# main.net
KiCad netlist of a schematic drawn in Altium Designer
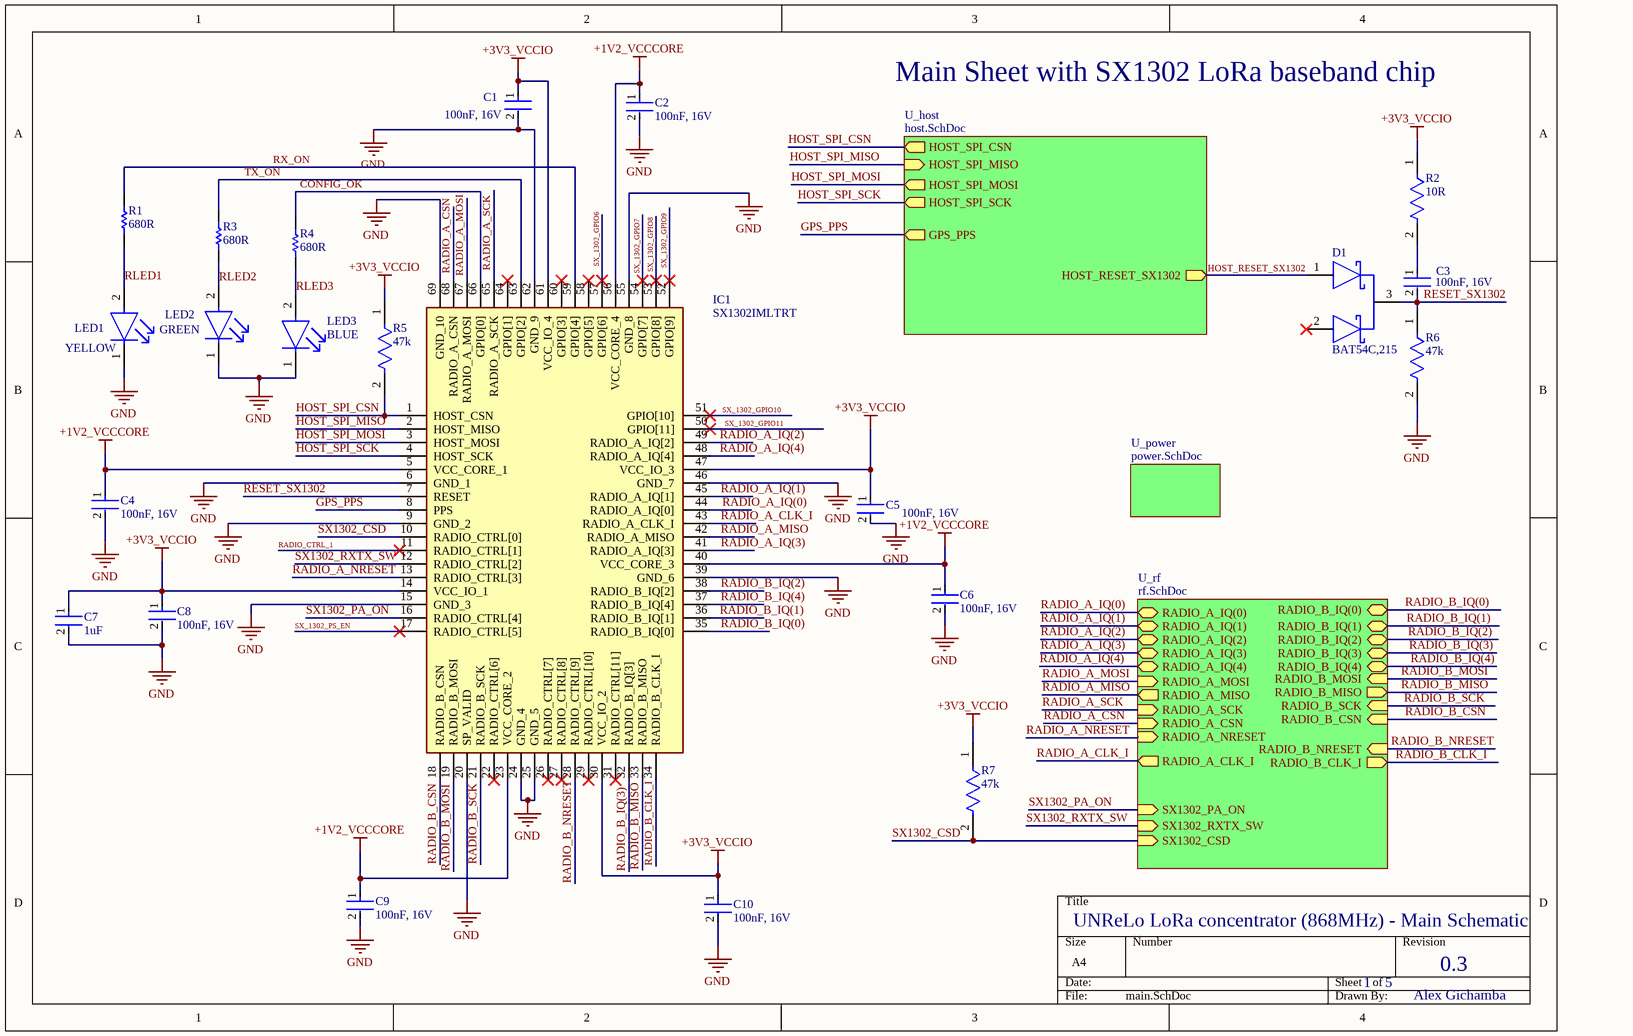
[diagram p0: main.SchDoc]

(export (version "E")
  (design (tool "Eeschema 10.0.6"))
  (components
    (comp (ref "C1")
      (value "100nF, 16V")
      (footprint "FP-CC0603-DA-MFG")
      (description "CAP CER 0.1UF 50V X7R 0603")
      (fields (field (name "MANUFACTURER") "YAGEO") (field (name "VOLTAGE") "50 V"))
      (libsource (lib "Altium Content Vault") (part "11868f565c42a9108669ba33697ecf6"))
    )
    (comp (ref "C2")
      (value "100nF, 16V")
      (footprint "FP-CC0603-DA-MFG")
      (description "CAP CER 0.1UF 50V X7R 0603")
      (fields (field (name "MANUFACTURER") "YAGEO") (field (name "VOLTAGE") "50 V"))
      (libsource (lib "Altium Content Vault") (part "11868f565c42a9108669ba33697ecf6"))
    )
    (comp (ref "C3")
      (value "100nF, 16V")
      (footprint "FP-CC0603-DA-MFG")
      (description "CAP CER 0.1UF 50V X7R 0603")
      (fields (field (name "MANUFACTURER") "YAGEO") (field (name "VOLTAGE") "50 V"))
      (libsource (lib "Altium Content Vault") (part "11868f565c42a9108669ba33697ecf6"))
    )
    (comp (ref "C4")
      (value "100nF, 16V")
      (footprint "FP-CC0603-DA-MFG")
      (description "CAP CER 0.1UF 50V X7R 0603")
      (fields (field (name "MANUFACTURER") "YAGEO") (field (name "VOLTAGE") "50 V"))
      (libsource (lib "Altium Content Vault") (part "11868f565c42a9108669ba33697ecf6"))
    )
    (comp (ref "C5")
      (value "100nF, 16V")
      (footprint "FP-CC0603-DA-MFG")
      (description "CAP CER 0.1UF 50V X7R 0603")
      (fields (field (name "MANUFACTURER") "YAGEO") (field (name "VOLTAGE") "50 V"))
      (libsource (lib "Altium Content Vault") (part "11868f565c42a9108669ba33697ecf6"))
    )
    (comp (ref "C6")
      (value "100nF, 16V")
      (footprint "FP-CC0603-DA-MFG")
      (description "CAP CER 0.1UF 50V X7R 0603")
      (fields (field (name "MANUFACTURER") "YAGEO") (field (name "VOLTAGE") "50 V"))
      (libsource (lib "Altium Content Vault") (part "11868f565c42a9108669ba33697ecf6"))
    )
    (comp (ref "C7")
      (value "1uF")
      (footprint "FP-CL21-IPC_A")
      (description "CL21 Series 0805 1uF 16V ±10% Tolerance X7R Multilayer Ceramic Chip Capacitor")
      (fields (field (name "TOLERANCE") "10%") (field (name "VOLTAGE") "16V"))
      (libsource (lib "Altium Content Vault") (part "b4654b650e69147ec39a6b967a45e02"))
    )
    (comp (ref "C8")
      (value "100nF, 16V")
      (footprint "FP-CC0603-DA-MFG")
      (description "CAP CER 0.1UF 50V X7R 0603")
      (fields (field (name "MANUFACTURER") "YAGEO") (field (name "VOLTAGE") "50 V"))
      (libsource (lib "Altium Content Vault") (part "11868f565c42a9108669ba33697ecf6"))
    )
    (comp (ref "C9")
      (value "100nF, 16V")
      (footprint "FP-CC0603-DA-MFG")
      (description "CAP CER 0.1UF 50V X7R 0603")
      (fields (field (name "MANUFACTURER") "YAGEO") (field (name "VOLTAGE") "50 V"))
      (libsource (lib "Altium Content Vault") (part "11868f565c42a9108669ba33697ecf6"))
    )
    (comp (ref "C10")
      (value "100nF, 16V")
      (footprint "FP-CC0603-DA-MFG")
      (description "CAP CER 0.1UF 50V X7R 0603")
      (fields (field (name "MANUFACTURER") "YAGEO") (field (name "VOLTAGE") "50 V"))
      (libsource (lib "Altium Content Vault") (part "11868f565c42a9108669ba33697ecf6"))
    )
    (comp (ref "D1")
      (value "BAT54C,215")
      (footprint "FP-SOT23-MFG")
      (description "DIODE ARRAY SCHOTTKY 30V SOT23")
      (fields
        (field (name "MANUFACTURER") "Nexperia")
        (field (name "OCTOPART") "https://octopart.com/bat54c%2C215-nexperia-78738945")
      )
      (libsource (lib "Altium Content Vault") (part "933c91619b22c421400e34e7415f7b4"))
    )
    (comp (ref "IC1")
      (value "SX1302IMLTRT")
      (footprint "QFN35P700X700X80-69N-D")
      (description "Integrated Circuit")
      (fields (field (name "MOUSER PART NUMBER") "947-SX1302IMLTRT"))
      (libsource (lib "Tafiti") (part "SX1302IMLTRT"))
    )
    (comp (ref "LED1")
      (value "YELLOW")
      (footprint "FP-SML-D12-MFG")
      (description "LED YLW/GREEN DIFFUSED 1608 SMD")
      (fields (field (name "MANUFACTURER PART NUMBER") "SML-D12M1WT86") (field (name "MANUFACTURER") "Rohm"))
      (libsource (lib "Altium Content Vault") (part "8706943c75ba83719d021d2fdc84c58"))
    )
    (comp (ref "LED2")
      (value "GREEN")
      (footprint "FP-LTST-C171GKT-MFG")
      (description "LED GREEN CLEAR CHIP SMD")
      (libsource (lib "Altium Content Vault") (part "8706943c75ba83719d021d2fdc84c58"))
    )
    (comp (ref "LED3")
      (value "BLUE")
      (footprint "FP-6_541-5094_01-4-MFG")
      (description "LED BLUE 0603 SMD")
      (fields
        (field (name "MANUFACTURER PART NUMBER") "VLMB1300-GS08")
        (field (name "MANUFACTURER") "Vishay Semiconductor Opto Division")
      )
      (libsource (lib "Altium Content Vault") (part "8706943c75ba83719d021d2fdc84c58"))
    )
    (comp (ref "R1")
      (value "680R")
      (footprint "RESC2013X70X40ML20T20")
      (fields (field (name "PART NUMBER") "ERJ6ENF6800V") (field (name "MANUFACTURER") "Panasonic"))
      (libsource (lib "Altium Content Vault") (part "RES"))
    )
    (comp (ref "R2")
      (value "10R")
      (footprint "FP-ERJ3EK-MFG")
      (description "RES SMD 10 OHM 1% 1/10W 0603")
      (fields
        (field (name "OCTOPART") "https://octopart.com/erj-3ekf10r0v-panasonic-55403649")
        (field (name "MANUFACTURER PART NUMBER") "ERJ-3EKF10R0V")
      )
      (libsource (lib "Altium Content Vault") (part "1029c3af85768c4190bb7ad29bc67b5"))
    )
    (comp (ref "R3")
      (value "680R")
      (footprint "RESC2013X70X40ML20T20")
      (fields (field (name "PART NUMBER") "ERJ6ENF6800V") (field (name "MANUFACTURER") "Panasonic"))
      (libsource (lib "Altium Content Vault") (part "RES"))
    )
    (comp (ref "R4")
      (value "680R")
      (footprint "RESC2013X70X40ML20T20")
      (fields (field (name "PART NUMBER") "ERJ6ENF6800V") (field (name "MANUFACTURER") "Panasonic"))
      (libsource (lib "Altium Content Vault") (part "RES"))
    )
    (comp (ref "R5")
      (value "47k")
      (footprint "FP-RMCF0805-IPC_B")
      (description "47kΩ ±5% 0.125W 0805 Thick Film Chip Resistor AEC-Q200 compliant")
      (fields (field (name "TOLERANCE") "5%"))
      (libsource (lib "Altium Content Vault") (part "1029c3af85768c4190bb7ad29bc67b5"))
    )
    (comp (ref "R6")
      (value "47k")
      (footprint "FP-RMCF0805-IPC_B")
      (description "47kΩ ±5% 0.125W 0805 Thick Film Chip Resistor AEC-Q200 compliant")
      (fields (field (name "TOLERANCE") "5%"))
      (libsource (lib "Altium Content Vault") (part "1029c3af85768c4190bb7ad29bc67b5"))
    )
    (comp (ref "R7")
      (value "47k")
      (footprint "FP-RMCF0805-IPC_B")
      (description "47kΩ ±5% 0.125W 0805 Thick Film Chip Resistor AEC-Q200 compliant")
      (fields (field (name "TOLERANCE") "5%"))
      (libsource (lib "Altium Content Vault") (part "1029c3af85768c4190bb7ad29bc67b5"))
    )
  )
  (nets
    (net (code "1") (name "+1V2_VCCCORE") (class "Default")
      (node (ref "C2") (pin "1") (pinfunction "1_1") (pintype "passive"))
      (node (ref "C4") (pin "1") (pinfunction "1_1") (pintype "passive"))
      (node (ref "C6") (pin "1") (pinfunction "1_1") (pintype "passive"))
      (node (ref "C9") (pin "1") (pinfunction "1_1") (pintype "passive"))
      (node (ref "IC1") (pin "23") (pinfunction "VCC_CORE_2_23") (pintype "passive"))
      (node (ref "IC1") (pin "40") (pinfunction "VCC_CORE_3_40") (pintype "passive"))
      (node (ref "IC1") (pin "5") (pinfunction "VCC_CORE_1_5") (pintype "passive"))
      (node (ref "IC1") (pin "56") (pinfunction "VCC_CORE_4_56") (pintype "passive"))
    )
    (net (code "2") (name "+3V3_VCCIO") (class "Default")
      (node (ref "C1") (pin "1") (pinfunction "1_1") (pintype "passive"))
      (node (ref "C10") (pin "1") (pinfunction "1_1") (pintype "passive"))
      (node (ref "C5") (pin "1") (pinfunction "1_1") (pintype "passive"))
      (node (ref "C7") (pin "1") (pinfunction "1_1") (pintype "passive"))
      (node (ref "C8") (pin "1") (pinfunction "1_1") (pintype "passive"))
      (node (ref "IC1") (pin "14") (pinfunction "VCC_IO_1_14") (pintype "passive"))
      (node (ref "IC1") (pin "30") (pinfunction "VCC_IO_2_30") (pintype "passive"))
      (node (ref "IC1") (pin "47") (pinfunction "VCC_IO_3_47") (pintype "passive"))
      (node (ref "IC1") (pin "61") (pinfunction "VCC_IO_4_61") (pintype "passive"))
      (node (ref "R2") (pin "1") (pinfunction "1_1") (pintype "passive"))
      (node (ref "R5") (pin "1") (pinfunction "1_1") (pintype "passive"))
      (node (ref "R7") (pin "1") (pinfunction "1_1") (pintype "passive"))
    )
    (net (code "3") (name "/CONFIG_OK") (class "Default")
      (node (ref "IC1") (pin "66") (pinfunction "GPIO[0]_66") (pintype "passive"))
      (node (ref "R4") (pin "2") (pinfunction "2_2") (pintype "passive"))
    )
    (net (code "4") (name "/GPS_PPS") (class "Default")
      (node (ref "IC1") (pin "8") (pinfunction "PPS_8") (pintype "passive"))
    )
    (net (code "5") (name "/HOST_RESET_SX1302") (class "Default")
      (node (ref "D1") (pin "1") (pinfunction "1_ANODE_1") (pintype "passive"))
    )
    (net (code "6") (name "/HOST_SPI_CSN") (class "Default")
      (node (ref "IC1") (pin "1") (pinfunction "HOST_CSN_1") (pintype "passive"))
      (node (ref "R5") (pin "2") (pinfunction "2_2") (pintype "passive"))
    )
    (net (code "7") (name "/HOST_SPI_MISO") (class "Default")
      (node (ref "IC1") (pin "2") (pinfunction "HOST_MISO_2") (pintype "passive"))
    )
    (net (code "8") (name "/HOST_SPI_MOSI") (class "Default")
      (node (ref "IC1") (pin "3") (pinfunction "HOST_MOSI_3") (pintype "passive"))
    )
    (net (code "9") (name "/HOST_SPI_SCK") (class "Default")
      (node (ref "IC1") (pin "4") (pinfunction "HOST_SCK_4") (pintype "passive"))
    )
    (net (code "10") (name "/RADIO_A_CLK_I") (class "Default")
      (node (ref "IC1") (pin "43") (pinfunction "RADIO_A_CLK_I_43") (pintype "passive"))
    )
    (net (code "11") (name "/RADIO_A_CSN") (class "Default")
      (node (ref "IC1") (pin "68") (pinfunction "RADIO_A_CSN_68") (pintype "passive"))
    )
    (net (code "12") (name "/RADIO_A_IQ(0)") (class "Default")
      (node (ref "IC1") (pin "44") (pinfunction "RADIO_A_IQ[0]_44") (pintype "passive"))
    )
    (net (code "13") (name "/RADIO_A_IQ(1)") (class "Default")
      (node (ref "IC1") (pin "45") (pinfunction "RADIO_A_IQ[1]_45") (pintype "passive"))
    )
    (net (code "14") (name "/RADIO_A_IQ(2)") (class "Default")
      (node (ref "IC1") (pin "49") (pinfunction "RADIO_A_IQ[2]_49") (pintype "passive"))
    )
    (net (code "15") (name "/RADIO_A_IQ(3)") (class "Default")
      (node (ref "IC1") (pin "41") (pinfunction "RADIO_A_IQ[3]_41") (pintype "passive"))
    )
    (net (code "16") (name "/RADIO_A_IQ(4)") (class "Default")
      (node (ref "IC1") (pin "48") (pinfunction "RADIO_A_IQ[4]_48") (pintype "passive"))
    )
    (net (code "17") (name "/RADIO_A_MISO") (class "Default")
      (node (ref "IC1") (pin "42") (pinfunction "RADIO_A_MISO_42") (pintype "passive"))
    )
    (net (code "18") (name "/RADIO_A_MOSI") (class "Default")
      (node (ref "IC1") (pin "67") (pinfunction "RADIO_A_MOSI_67") (pintype "passive"))
    )
    (net (code "19") (name "/RADIO_A_NRESET") (class "Default")
      (node (ref "IC1") (pin "13") (pinfunction "RADIO_CTRL[3]_13") (pintype "passive"))
    )
    (net (code "20") (name "/RADIO_A_SCK") (class "Default")
      (node (ref "IC1") (pin "65") (pinfunction "RADIO_A_SCK_65") (pintype "passive"))
    )
    (net (code "21") (name "/RADIO_B_CLK_I") (class "Default")
      (node (ref "IC1") (pin "34") (pinfunction "RADIO_B_CLK_I_34") (pintype "passive"))
    )
    (net (code "22") (name "/RADIO_B_CSN") (class "Default")
      (node (ref "IC1") (pin "18") (pinfunction "RADIO_B_CSN_18") (pintype "passive"))
    )
    (net (code "23") (name "/RADIO_B_IQ(0)") (class "Default")
      (node (ref "IC1") (pin "35") (pinfunction "RADIO_B_IQ[0]_35") (pintype "passive"))
    )
    (net (code "24") (name "/RADIO_B_IQ(1)") (class "Default")
      (node (ref "IC1") (pin "36") (pinfunction "RADIO_B_IQ[1]_36") (pintype "passive"))
    )
    (net (code "25") (name "/RADIO_B_IQ(2)") (class "Default")
      (node (ref "IC1") (pin "38") (pinfunction "RADIO_B_IQ[2]_38") (pintype "passive"))
    )
    (net (code "26") (name "/RADIO_B_IQ(3)") (class "Default")
      (node (ref "IC1") (pin "32") (pinfunction "RADIO_B_IQ[3]_32") (pintype "passive"))
    )
    (net (code "27") (name "/RADIO_B_IQ(4)") (class "Default")
      (node (ref "IC1") (pin "37") (pinfunction "RADIO_B_IQ[4]_37") (pintype "passive"))
    )
    (net (code "28") (name "/RADIO_B_MISO") (class "Default")
      (node (ref "IC1") (pin "33") (pinfunction "RADIO_B_MISO_33") (pintype "passive"))
    )
    (net (code "29") (name "/RADIO_B_MOSI") (class "Default")
      (node (ref "IC1") (pin "19") (pinfunction "RADIO_B_MOSI_19") (pintype "passive"))
    )
    (net (code "30") (name "/RADIO_B_NRESET") (class "Default")
      (node (ref "IC1") (pin "28") (pinfunction "RADIO_CTRL[9]_28") (pintype "passive"))
    )
    (net (code "31") (name "/RADIO_B_SCK") (class "Default")
      (node (ref "IC1") (pin "21") (pinfunction "RADIO_B_SCK_21") (pintype "passive"))
    )
    (net (code "32") (name "/RADIO_CTRL_1") (class "Default")
      (node (ref "IC1") (pin "11") (pinfunction "RADIO_CTRL[1]_11") (pintype "passive+no_connect"))
    )
    (net (code "33") (name "/RESET_SX1302") (class "Default")
      (node (ref "C3") (pin "2") (pinfunction "2_2") (pintype "passive"))
      (node (ref "D1") (pin "3") (pinfunction "COMMON_CATHODE_3") (pintype "passive"))
      (node (ref "IC1") (pin "7") (pinfunction "RESET_7") (pintype "passive"))
      (node (ref "R6") (pin "1") (pinfunction "1_1") (pintype "passive"))
    )
    (net (code "34") (name "/RLED1") (class "Default")
      (node (ref "LED1") (pin "2") (pinfunction "A_2") (pintype "passive"))
      (node (ref "R1") (pin "1") (pinfunction "1_1") (pintype "passive"))
    )
    (net (code "35") (name "/RLED2") (class "Default")
      (node (ref "LED2") (pin "2") (pinfunction "A_2") (pintype "passive"))
      (node (ref "R3") (pin "1") (pinfunction "1_1") (pintype "passive"))
    )
    (net (code "36") (name "/RLED3") (class "Default")
      (node (ref "LED3") (pin "2") (pinfunction "A_2") (pintype "passive"))
      (node (ref "R4") (pin "1") (pinfunction "1_1") (pintype "passive"))
    )
    (net (code "37") (name "/RX_ON") (class "Default")
      (node (ref "IC1") (pin "59") (pinfunction "GPIO[4]_59") (pintype "passive"))
      (node (ref "R1") (pin "2") (pinfunction "2_2") (pintype "passive"))
    )
    (net (code "38") (name "/SX1302_CSD") (class "Default")
      (node (ref "IC1") (pin "10") (pinfunction "RADIO_CTRL[0]_10") (pintype "passive"))
      (node (ref "R7") (pin "2") (pinfunction "2_2") (pintype "passive"))
    )
    (net (code "39") (name "/SX1302_PA_ON") (class "Default")
      (node (ref "IC1") (pin "16") (pinfunction "RADIO_CTRL[4]_16") (pintype "passive"))
    )
    (net (code "40") (name "/SX1302_RXTX_SW") (class "Default")
      (node (ref "IC1") (pin "12") (pinfunction "RADIO_CTRL[2]_12") (pintype "passive"))
    )
    (net (code "41") (name "/SX_1302_GPIO6") (class "Default")
      (node (ref "IC1") (pin "57") (pinfunction "GPIO[6]_57") (pintype "passive+no_connect"))
    )
    (net (code "42") (name "/SX_1302_GPIO7") (class "Default")
      (node (ref "IC1") (pin "54") (pinfunction "GPIO[7]_54") (pintype "passive+no_connect"))
    )
    (net (code "43") (name "/SX_1302_GPIO8") (class "Default")
      (node (ref "IC1") (pin "53") (pinfunction "GPIO[8]_53") (pintype "passive+no_connect"))
    )
    (net (code "44") (name "/SX_1302_GPIO9") (class "Default")
      (node (ref "IC1") (pin "52") (pinfunction "GPIO[9]_52") (pintype "passive+no_connect"))
    )
    (net (code "45") (name "/SX_1302_GPIO10") (class "Default")
      (node (ref "IC1") (pin "51") (pinfunction "GPIO[10]_51") (pintype "passive+no_connect"))
    )
    (net (code "46") (name "/SX_1302_GPIO11") (class "Default")
      (node (ref "IC1") (pin "50") (pinfunction "GPIO[11]_50") (pintype "passive+no_connect"))
    )
    (net (code "47") (name "/SX_1302_PS_EN") (class "Default")
      (node (ref "IC1") (pin "17") (pinfunction "RADIO_CTRL[5]_17") (pintype "passive+no_connect"))
    )
    (net (code "48") (name "/TX_ON") (class "Default")
      (node (ref "IC1") (pin "63") (pinfunction "GPIO[2]_63") (pintype "passive"))
      (node (ref "R3") (pin "2") (pinfunction "2_2") (pintype "passive"))
    )
    (net (code "49") (name "GND") (class "Default")
      (node (ref "C1") (pin "2") (pinfunction "2_2") (pintype "passive"))
      (node (ref "C10") (pin "2") (pinfunction "2_2") (pintype "passive"))
      (node (ref "C2") (pin "2") (pinfunction "2_2") (pintype "passive"))
      (node (ref "C4") (pin "2") (pinfunction "2_2") (pintype "passive"))
      (node (ref "C5") (pin "2") (pinfunction "2_2") (pintype "passive"))
      (node (ref "C6") (pin "2") (pinfunction "2_2") (pintype "passive"))
      (node (ref "C7") (pin "2") (pinfunction "2_2") (pintype "passive"))
      (node (ref "C8") (pin "2") (pinfunction "2_2") (pintype "passive"))
      (node (ref "C9") (pin "2") (pinfunction "2_2") (pintype "passive"))
      (node (ref "IC1") (pin "15") (pinfunction "GND_3_15") (pintype "passive"))
      (node (ref "IC1") (pin "20") (pinfunction "SP_VALID_20") (pintype "passive"))
      (node (ref "IC1") (pin "24") (pinfunction "GND_4_24") (pintype "passive"))
      (node (ref "IC1") (pin "25") (pinfunction "GND_5_25") (pintype "passive"))
      (node (ref "IC1") (pin "39") (pinfunction "GND_6_39") (pintype "passive"))
      (node (ref "IC1") (pin "46") (pinfunction "GND_7_46") (pintype "passive"))
      (node (ref "IC1") (pin "55") (pinfunction "GND_8_55") (pintype "passive"))
      (node (ref "IC1") (pin "6") (pinfunction "GND_1_6") (pintype "passive"))
      (node (ref "IC1") (pin "62") (pinfunction "GND_9_62") (pintype "passive"))
      (node (ref "IC1") (pin "69") (pinfunction "GND_10_69") (pintype "passive"))
      (node (ref "IC1") (pin "9") (pinfunction "GND_2_9") (pintype "passive"))
      (node (ref "LED1") (pin "1") (pinfunction "C_1") (pintype "passive"))
      (node (ref "LED2") (pin "1") (pinfunction "C_1") (pintype "passive"))
      (node (ref "LED3") (pin "1") (pinfunction "C_1") (pintype "passive"))
      (node (ref "R6") (pin "2") (pinfunction "2_2") (pintype "passive"))
    )
    (net (code "50") (name "Net-(C3-Pad1)") (class "Default")
      (node (ref "C3") (pin "1") (pinfunction "1_1") (pintype "passive"))
      (node (ref "R2") (pin "2") (pinfunction "2_2") (pintype "passive"))
    )
    (net (code "51") (name "unconnected-(D1-2_ANODE-Pad2)") (class "Default")
      (node (ref "D1") (pin "2") (pinfunction "2_ANODE_2") (pintype "passive+no_connect"))
    )
    (net (code "52") (name "unconnected-(IC1-GPIO[1]-Pad64)") (class "Default")
      (node (ref "IC1") (pin "64") (pinfunction "GPIO[1]_64") (pintype "passive+no_connect"))
    )
    (net (code "53") (name "unconnected-(IC1-GPIO[3]-Pad60)") (class "Default")
      (node (ref "IC1") (pin "60") (pinfunction "GPIO[3]_60") (pintype "passive+no_connect"))
    )
    (net (code "54") (name "unconnected-(IC1-GPIO[5]-Pad58)") (class "Default")
      (node (ref "IC1") (pin "58") (pinfunction "GPIO[5]_58") (pintype "passive+no_connect"))
    )
    (net (code "55") (name "unconnected-(IC1-RADIO_CTRL[6]-Pad22)") (class "Default")
      (node (ref "IC1") (pin "22") (pinfunction "RADIO_CTRL[6]_22") (pintype "passive+no_connect"))
    )
    (net (code "56") (name "unconnected-(IC1-RADIO_CTRL[7]-Pad26)") (class "Default")
      (node (ref "IC1") (pin "26") (pinfunction "RADIO_CTRL[7]_26") (pintype "passive+no_connect"))
    )
    (net (code "57") (name "unconnected-(IC1-RADIO_CTRL[8]-Pad27)") (class "Default")
      (node (ref "IC1") (pin "27") (pinfunction "RADIO_CTRL[8]_27") (pintype "passive+no_connect"))
    )
    (net (code "58") (name "unconnected-(IC1-RADIO_CTRL[10]-Pad29)") (class "Default")
      (node (ref "IC1") (pin "29") (pinfunction "RADIO_CTRL[10]_29") (pintype "passive+no_connect"))
    )
    (net (code "59") (name "unconnected-(IC1-RADIO_CTRL[11]-Pad31)") (class "Default")
      (node (ref "IC1") (pin "31") (pinfunction "RADIO_CTRL[11]_31") (pintype "passive+no_connect"))
    )
  )
)
